# dual_monostable.net
KiCad netlist of a schematic drawn in Altium Designer
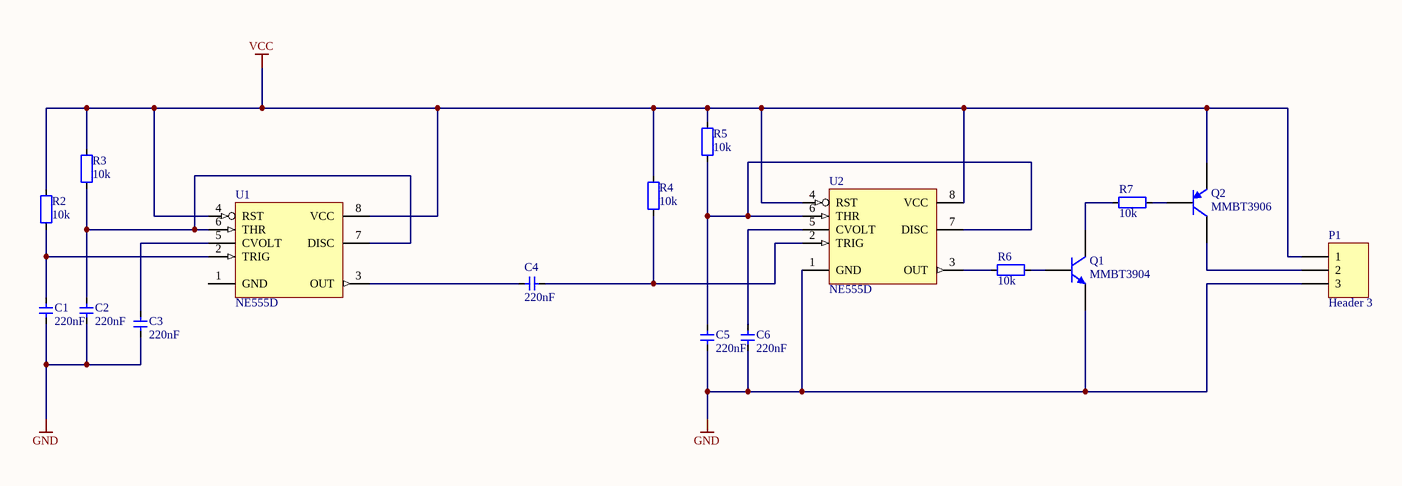
[diagram p0: dual monostable.SchDoc]

(export (version "E")
  (design (tool "Eeschema 10.0.6"))
  (components
    (comp (ref "C1")
      (value "220nF")
      (footprint "PCB_PassiveCap:CAP_0603")
      (description "Capacitor")
      (fields (field (name "Comment") "Cap_0603"))
      (libsource (lib "SCH_Passive") (part "Cap_0603"))
    )
    (comp (ref "C2")
      (value "220nF")
      (footprint "PCB_PassiveCap:CAP_0603")
      (description "Capacitor")
      (fields (field (name "Comment") "Cap_0603"))
      (libsource (lib "SCH_Passive") (part "Cap_0603"))
    )
    (comp (ref "C3")
      (value "220nF")
      (footprint "PCB_PassiveCap:CAP_0603")
      (description "Capacitor")
      (fields (field (name "Comment") "Cap_0603"))
      (libsource (lib "SCH_Passive") (part "Cap_0603"))
    )
    (comp (ref "C4")
      (value "220nF")
      (footprint "PCB_PassiveCap:CAP_0603")
      (description "Capacitor")
      (fields (field (name "Comment") "Cap_0603"))
      (libsource (lib "SCH_Passive") (part "Cap_0603"))
    )
    (comp (ref "C5")
      (value "220nF")
      (footprint "PCB_PassiveCap:CAP_0603")
      (description "Capacitor")
      (fields (field (name "Comment") "Cap_0603"))
      (libsource (lib "SCH_Passive") (part "Cap_0603"))
    )
    (comp (ref "C6")
      (value "220nF")
      (footprint "PCB_PassiveCap:CAP_0603")
      (description "Capacitor")
      (fields (field (name "Comment") "Cap_0603"))
      (libsource (lib "SCH_Passive") (part "Cap_0603"))
    )
    (comp (ref "P1")
      (value "Header 3")
      (footprint "HDR1X3")
      (description "Header, 3-Pin")
      (fields (field (name "PUBLISHER") "Altium Limited"))
      (libsource (lib "Miscellaneous Connectors") (part "Header 3"))
    )
    (comp (ref "Q1")
      (value "MMBT3904")
      (footprint "SOT23_N")
      (description "NPN Switching Transistor")
      (fields (field (name "PUBLISHER") "Altium Limited"))
      (libsource (lib "Philips Discrete BJT - Low Power") (part "MMBT3904"))
    )
    (comp (ref "Q2")
      (value "MMBT3906")
      (footprint "SOT23_N")
      (description "PNP Switching Transistor")
      (fields (field (name "PUBLISHER") "Altium Limited"))
      (libsource (lib "Philips Discrete BJT - Low Power") (part "MMBT3906"))
    )
    (comp (ref "R2")
      (value "10k")
      (footprint "PCB_PassiveRes:RES_0603")
      (description "Resistor")
      (fields (field (name "Comment") "Res_0603"))
      (libsource (lib "SCH_Passive") (part "Res_0603"))
    )
    (comp (ref "R3")
      (value "10k")
      (footprint "PCB_PassiveRes:RES_0603")
      (description "Resistor")
      (fields (field (name "Comment") "Res_0603"))
      (libsource (lib "SCH_Passive") (part "Res_0603"))
    )
    (comp (ref "R4")
      (value "10k")
      (footprint "PCB_PassiveRes:RES_0603")
      (description "Resistor")
      (fields (field (name "Comment") "Res_0603"))
      (libsource (lib "SCH_Passive") (part "Res_0603"))
    )
    (comp (ref "R5")
      (value "10k")
      (footprint "PCB_PassiveRes:RES_0603")
      (description "Resistor")
      (fields (field (name "Comment") "Res_0603"))
      (libsource (lib "SCH_Passive") (part "Res_0603"))
    )
    (comp (ref "R6")
      (value "10k")
      (footprint "PCB_PassiveRes:RES_0603")
      (description "Resistor")
      (fields (field (name "Comment") "Res_0603"))
      (libsource (lib "") (part "Res_0603_1"))
    )
    (comp (ref "R7")
      (value "10k")
      (footprint "PCB_PassiveRes:RES_0603")
      (description "Resistor")
      (fields (field (name "Comment") "Res_0603"))
      (libsource (lib "") (part "Res_0603_1"))
    )
    (comp (ref "U1")
      (value "NE555D")
      (footprint "D008_N")
      (description "Precision Timer")
      (fields (field (name "PUBLISHER") "Altium Limited"))
      (libsource (lib "TI Analog Timer Circuit") (part "NE555D"))
    )
    (comp (ref "U2")
      (value "NE555D")
      (footprint "D008_N")
      (description "Precision Timer")
      (fields (field (name "PUBLISHER") "Altium Limited"))
      (libsource (lib "TI Analog Timer Circuit") (part "NE555D"))
    )
  )
  (nets
    (net (code "1") (name "GND") (class "Default")
      (node (ref "C1") (pin "2") (pinfunction "2_2") (pintype "passive"))
      (node (ref "C2") (pin "1") (pinfunction "1_1") (pintype "passive"))
      (node (ref "C3") (pin "1") (pinfunction "1_1") (pintype "passive"))
      (node (ref "C5") (pin "1") (pinfunction "1_1") (pintype "passive"))
      (node (ref "C6") (pin "1") (pinfunction "1_1") (pintype "passive"))
      (node (ref "P1") (pin "3") (pinfunction "3_3") (pintype "passive"))
      (node (ref "Q1") (pin "2") (pinfunction "E_2") (pintype "passive"))
      (node (ref "U2") (pin "1") (pinfunction "GND_1") (pintype "power_in"))
    )
    (net (code "2") (name "Net-(Q1-B)") (class "Default")
      (node (ref "Q1") (pin "1") (pinfunction "B_1") (pintype "passive"))
      (node (ref "R6") (pin "1") (pinfunction "1_1") (pintype "passive"))
    )
    (net (code "3") (name "Net-(Q1-C)") (class "Default")
      (node (ref "Q1") (pin "3") (pinfunction "C_3") (pintype "passive"))
      (node (ref "R7") (pin "2") (pinfunction "2_2") (pintype "passive"))
    )
    (net (code "4") (name "Net-(Q2-B)") (class "Default")
      (node (ref "Q2") (pin "1") (pinfunction "B_1") (pintype "passive"))
      (node (ref "R7") (pin "1") (pinfunction "1_1") (pintype "passive"))
    )
    (net (code "5") (name "Net-(Q2-C)") (class "Default")
      (node (ref "P1") (pin "2") (pinfunction "2_2") (pintype "passive"))
      (node (ref "Q2") (pin "3") (pinfunction "C_3") (pintype "passive"))
    )
    (net (code "6") (name "Net-(U1-CVOLT)") (class "Default")
      (node (ref "C3") (pin "2") (pinfunction "2_2") (pintype "passive"))
      (node (ref "U1") (pin "5") (pinfunction "CVOLT_5") (pintype "passive"))
    )
    (net (code "7") (name "Net-(U1-DISC)") (class "Default")
      (node (ref "C2") (pin "2") (pinfunction "2_2") (pintype "passive"))
      (node (ref "R3") (pin "1") (pinfunction "1_1") (pintype "passive"))
      (node (ref "U1") (pin "6") (pinfunction "THR_6") (pintype "input"))
      (node (ref "U1") (pin "7") (pinfunction "DISC_7") (pintype "open_collector"))
    )
    (net (code "8") (name "Net-(U1-OUT)") (class "Default")
      (node (ref "C4") (pin "2") (pinfunction "2_2") (pintype "passive"))
      (node (ref "U1") (pin "3") (pinfunction "OUT_3") (pintype "output"))
    )
    (net (code "9") (name "Net-(U1-TRIG)") (class "Default")
      (node (ref "C1") (pin "1") (pinfunction "1_1") (pintype "passive"))
      (node (ref "R2") (pin "1") (pinfunction "1_1") (pintype "passive"))
      (node (ref "U1") (pin "2") (pinfunction "TRIG_2") (pintype "input"))
    )
    (net (code "10") (name "Net-(U2-CVOLT)") (class "Default")
      (node (ref "C6") (pin "2") (pinfunction "2_2") (pintype "passive"))
      (node (ref "U2") (pin "5") (pinfunction "CVOLT_5") (pintype "passive"))
    )
    (net (code "11") (name "Net-(U2-DISC)") (class "Default")
      (node (ref "C5") (pin "2") (pinfunction "2_2") (pintype "passive"))
      (node (ref "R5") (pin "1") (pinfunction "1_1") (pintype "passive"))
      (node (ref "U2") (pin "6") (pinfunction "THR_6") (pintype "input"))
      (node (ref "U2") (pin "7") (pinfunction "DISC_7") (pintype "open_collector"))
    )
    (net (code "12") (name "Net-(U2-OUT)") (class "Default")
      (node (ref "R6") (pin "2") (pinfunction "2_2") (pintype "passive"))
      (node (ref "U2") (pin "3") (pinfunction "OUT_3") (pintype "output"))
    )
    (net (code "13") (name "Net-(U2-TRIG)") (class "Default")
      (node (ref "C4") (pin "1") (pinfunction "1_1") (pintype "passive"))
      (node (ref "R4") (pin "1") (pinfunction "1_1") (pintype "passive"))
      (node (ref "U2") (pin "2") (pinfunction "TRIG_2") (pintype "input"))
    )
    (net (code "14") (name "VCC") (class "Default")
      (node (ref "P1") (pin "1") (pinfunction "1_1") (pintype "passive"))
      (node (ref "Q2") (pin "2") (pinfunction "E_2") (pintype "passive"))
      (node (ref "R2") (pin "2") (pinfunction "2_2") (pintype "passive"))
      (node (ref "R3") (pin "2") (pinfunction "2_2") (pintype "passive"))
      (node (ref "R4") (pin "2") (pinfunction "2_2") (pintype "passive"))
      (node (ref "R5") (pin "2") (pinfunction "2_2") (pintype "passive"))
      (node (ref "U1") (pin "4") (pinfunction "RST_4") (pintype "input"))
      (node (ref "U1") (pin "8") (pinfunction "VCC_8") (pintype "power_in"))
      (node (ref "U2") (pin "4") (pinfunction "RST_4") (pintype "input"))
      (node (ref "U2") (pin "8") (pinfunction "VCC_8") (pintype "power_in"))
    )
    (net (code "15") (name "unconnected-(U1-GND-Pad1)") (class "Default")
      (node (ref "U1") (pin "1") (pinfunction "GND_1") (pintype "power_in"))
    )
  )
)
